# BMD101circuits.net
KiCad netlist of a schematic drawn in Altium Designer
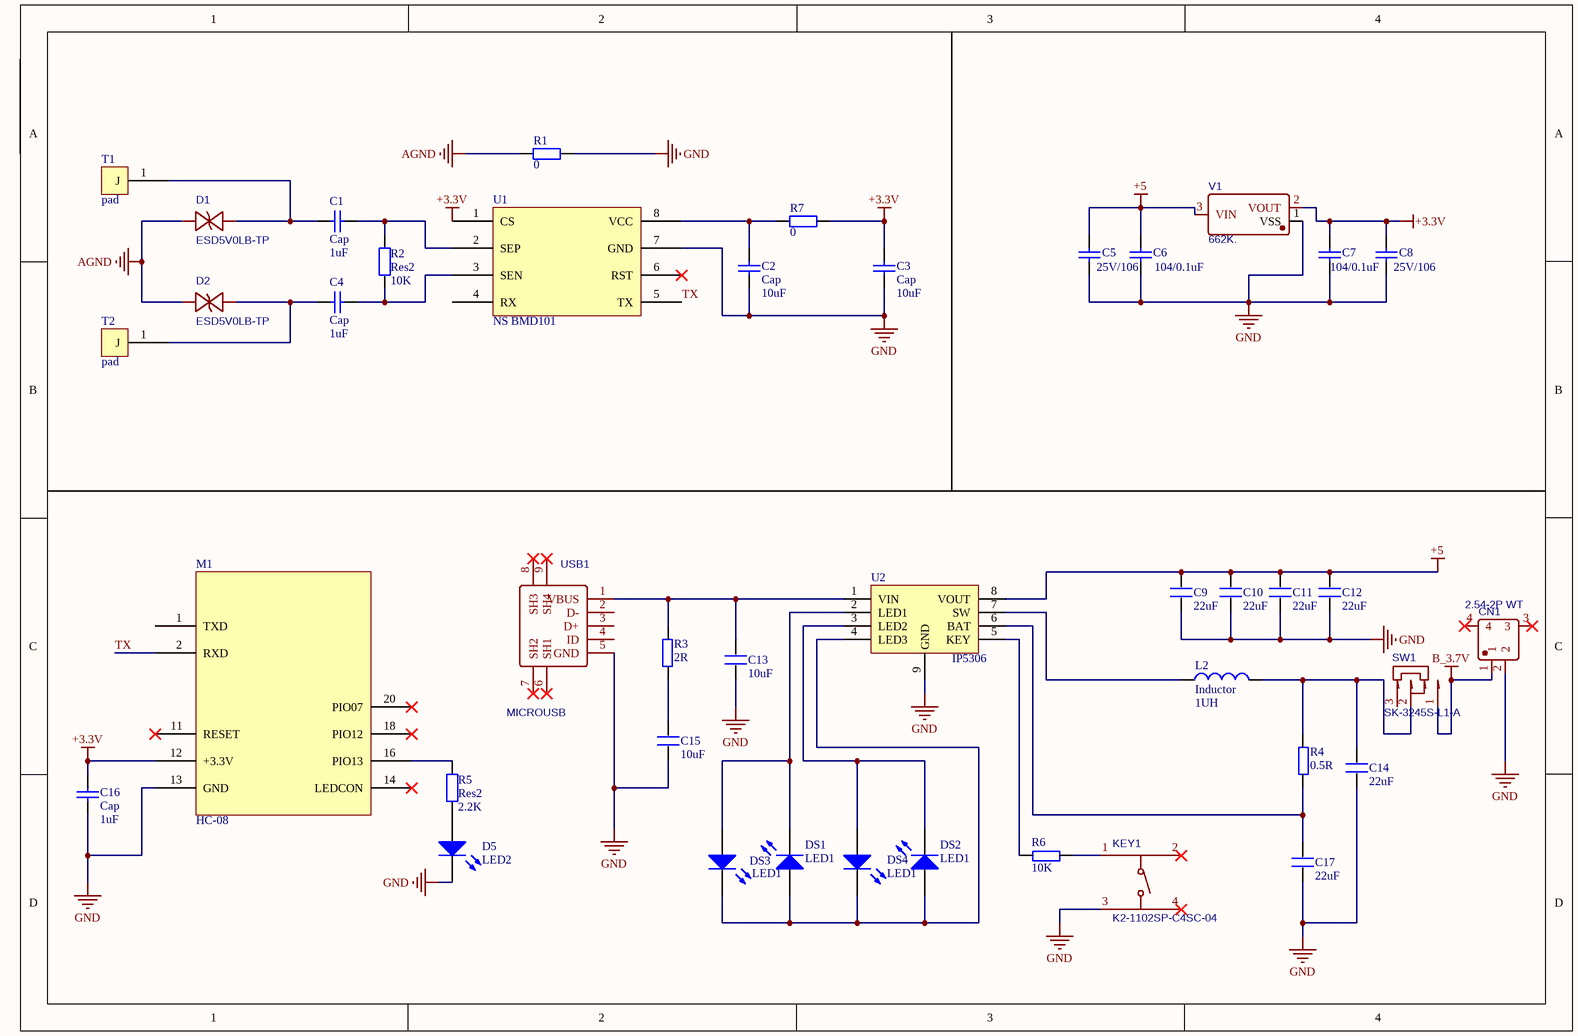
[diagram p0: BMD101circuits.SchDoc]

(export (version "E")
  (design (tool "Eeschema 10.0.6"))
  (components
    (comp (ref "C1")
      (value "Cap")
      (footprint "J1-0603")
      (description "Capacitor")
      (fields (field (name "ALTIUM_VALUE") "1uF") (field (name "PUBLISHER") "Altium Limited"))
      (libsource (lib "Miscellaneous Devices") (part "Cap"))
    )
    (comp (ref "C2")
      (value "Cap")
      (footprint "J1-0603")
      (description "Capacitor")
      (fields (field (name "ALTIUM_VALUE") "10uF") (field (name "PUBLISHER") "Altium Limited"))
      (libsource (lib "Miscellaneous Devices") (part "Cap"))
    )
    (comp (ref "C3")
      (value "Cap")
      (footprint "J1-0603")
      (description "Capacitor")
      (fields (field (name "ALTIUM_VALUE") "10uF") (field (name "PUBLISHER") "Altium Limited"))
      (libsource (lib "Miscellaneous Devices") (part "Cap"))
    )
    (comp (ref "C4")
      (value "Cap")
      (footprint "J1-0603")
      (description "Capacitor")
      (fields (field (name "ALTIUM_VALUE") "1uF") (field (name "PUBLISHER") "Altium Limited"))
      (libsource (lib "Miscellaneous Devices") (part "Cap"))
    )
    (comp (ref "C5")
      (value "25V/106")
      (footprint "J1-0603")
      (description "Capacitor")
      (fields (field (name "PUBLISHER") "Altium Limited"))
      (libsource (lib "Miscellaneous Devices") (part "Cap"))
    )
    (comp (ref "C6")
      (value "104/0.1uF")
      (footprint "J1-0603")
      (description "Capacitor")
      (fields (field (name "Comment") "104") (field (name "PUBLISHER") "Altium Limited"))
      (libsource (lib "Miscellaneous Devices") (part "Cap"))
    )
    (comp (ref "C7")
      (value "104/0.1uF")
      (footprint "J1-0603")
      (description "Capacitor")
      (fields (field (name "Comment") "104") (field (name "PUBLISHER") "Altium Limited"))
      (libsource (lib "Miscellaneous Devices") (part "Cap"))
    )
    (comp (ref "C8")
      (value "25V/106")
      (footprint "J1-0603")
      (description "Capacitor")
      (fields (field (name "PUBLISHER") "Altium Limited"))
      (libsource (lib "Miscellaneous Devices") (part "Cap"))
    )
    (comp (ref "C9")
      (value "22uF")
      (footprint "J1-0603")
      (description "0805")
      (libsource (lib "power") (part "C_22"))
    )
    (comp (ref "C10")
      (value "22uF")
      (footprint "J1-0603")
      (description "0805")
      (libsource (lib "power") (part "C_22"))
    )
    (comp (ref "C11")
      (value "22uF")
      (footprint "J1-0603")
      (description "0805")
      (libsource (lib "power") (part "C_22"))
    )
    (comp (ref "C12")
      (value "22uF")
      (footprint "J1-0603")
      (description "0805")
      (libsource (lib "power") (part "C_22"))
    )
    (comp (ref "C13")
      (value "10uF")
      (footprint "J1-0603")
      (description "0805")
      (libsource (lib "power") (part "C_22"))
    )
    (comp (ref "C14")
      (value "22uF")
      (footprint "J1-0603")
      (description "0805")
      (libsource (lib "power") (part "C_22"))
    )
    (comp (ref "C15")
      (value "10uF")
      (footprint "Miscellaneous Devices:J1-0603")
      (description "0805")
      (libsource (lib "power") (part "C_22"))
    )
    (comp (ref "C16")
      (value "Cap")
      (footprint "J1-0603")
      (description "Capacitor")
      (fields (field (name "ALTIUM_VALUE") "1uF") (field (name "PUBLISHER") "Altium Limited"))
      (libsource (lib "Miscellaneous Devices") (part "Cap"))
    )
    (comp (ref "C17")
      (value "22uF")
      (footprint "J1-0603")
      (description "0805")
      (libsource (lib "power") (part "C_22"))
    )
    (comp (ref "CN1")
      (value "2.54-2P WT")
      (footprint "CONN-SMD_2.54-2PWT")
      (fields (field (name "BOM_SUPPLIER PART") "C668622") (field (name "CONTRIBUTOR") "LCSC"))
      (libsource (lib "毕业设计") (part "2.54-2P WT"))
    )
    (comp (ref "D1")
      (value "ESD5V0LB-TP")
      (footprint "ESD5V0D5B")
      (fields (field (name "BOM_SUPPLIER PART") "C668927") (field (name "CONTRIBUTOR") "LCSC"))
      (libsource (lib "altium-import") (part "root_0_ESD5V0LB-TP_"))
    )
    (comp (ref "D2")
      (value "ESD5V0LB-TP")
      (footprint "ESD5V0D5B")
      (fields (field (name "BOM_SUPPLIER PART") "C668927") (field (name "CONTRIBUTOR") "LCSC"))
      (libsource (lib "altium-import") (part "root_2_ESD5V0LB-TP_"))
    )
    (comp (ref "D5")
      (value "LED2")
      (footprint "LED0603-FD")
      (description "Typical RED, GREEN, YELLOW, AMBER GaAs LED")
      (fields (field (name "PUBLISHER") "Altium Limited"))
      (libsource (lib "Miscellaneous Devices") (part "LED2"))
    )
    (comp (ref "DS1")
      (value "LED1")
      (footprint "LED0603-FD")
      (description "Typical RED, GREEN, YELLOW, AMBER GaAs LED")
      (fields (field (name "PUBLISHER") "Altium Limited"))
      (libsource (lib "power") (part "LED2"))
    )
    (comp (ref "DS2")
      (value "LED1")
      (footprint "LED0603-FD")
      (description "Typical RED, GREEN, YELLOW, AMBER GaAs LED")
      (fields (field (name "PUBLISHER") "Altium Limited"))
      (libsource (lib "power") (part "LED2"))
    )
    (comp (ref "DS3")
      (value "LED1")
      (footprint "LED0603-FD")
      (description "Typical RED, GREEN, YELLOW, AMBER GaAs LED")
      (fields (field (name "PUBLISHER") "Altium Limited"))
      (libsource (lib "power") (part "LED2"))
    )
    (comp (ref "DS4")
      (value "LED1")
      (footprint "LED0603-FD")
      (description "Typical RED, GREEN, YELLOW, AMBER GaAs LED")
      (fields (field (name "PUBLISHER") "Altium Limited"))
      (libsource (lib "power") (part "LED2"))
    )
    (comp (ref "KEY1")
      (value "K2-1102SP-C4SC-04")
      (footprint "KEY-SMD_4P-L6.0-W6.0-P4.50-LS9.5-BL")
      (fields (field (name "BOM_SUPPLIER PART") "C127509") (field (name "CONTRIBUTOR") "LCSC"))
      (libsource (lib "毕业设计") (part "K2-1102SP-C4SC-04"))
    )
    (comp (ref "L2")
      (value "Inductor")
      (footprint "J1-0603")
      (fields (field (name "ALTIUM_VALUE") "1UH") (field (name "PUBLISHER") "Altium Limited"))
      (libsource (lib "power") (part "Inductor"))
    )
    (comp (ref "M1")
      (value "HC-08")
      (footprint "HC-08")
      (description "BLE蓝牙通信模块")
      (libsource (lib "毕业设计") (part "HC-08"))
    )
    (comp (ref "R1")
      (value "0")
      (footprint "J1-0603")
      (description "Resistor")
      (fields (field (name "Comment") "10K") (field (name "PUBLISHER") "Altium Limited"))
      (libsource (lib "原理图库") (part "Res2"))
    )
    (comp (ref "R2")
      (value "Res2")
      (footprint "J1-0603")
      (description "Resistor")
      (fields (field (name "ALTIUM_VALUE") "10K") (field (name "PUBLISHER") "Altium Limited"))
      (libsource (lib "Miscellaneous Devices") (part "Res2"))
    )
    (comp (ref "R3")
      (value "2R")
      (footprint "Miscellaneous Devices:J1-0603")
      (libsource (lib "power") (part "R_2"))
    )
    (comp (ref "R4") (value "0.5R") (footprint "J1-0603") (libsource (lib "power") (part "R_2")))
    (comp (ref "R5")
      (value "Res2")
      (footprint "J1-0603")
      (description "Resistor")
      (fields (field (name "ALTIUM_VALUE") "2.2K") (field (name "PUBLISHER") "Altium Limited"))
      (libsource (lib "Miscellaneous Devices") (part "Res2"))
    )
    (comp (ref "R6") (value "10K") (footprint "J1-0603") (libsource (lib "power") (part "R_2")))
    (comp (ref "R7")
      (value "0")
      (footprint "J1-0603")
      (description "Resistor")
      (fields (field (name "Comment") "10K") (field (name "PUBLISHER") "Altium Limited"))
      (libsource (lib "原理图库") (part "Res2"))
    )
    (comp (ref "SW1")
      (value "SK-3245S-L1-A")
      (footprint "SW-SMD_SK-3245S-L1-A-1")
      (description "卧式滑动开关")
      (fields (field (name "BOM_SUPPLIER PART") "C405951") (field (name "CONTRIBUTOR") "LCSC"))
      (libsource (lib "毕业设计") (part "SK-3245S-L1-A"))
    )
    (comp (ref "T1") (value "pad") (footprint "BATOO") (libsource (lib "毕业设计") (part "BATOO")))
    (comp (ref "T2") (value "pad") (footprint "BATOO") (libsource (lib "毕业设计") (part "BATOO")))
    (comp (ref "U1")
      (value "NS BMD101")
      (footprint "BMD101")
      (description "NeuroSky心率芯片")
      (libsource (lib "毕业设计") (part "BMD101"))
    )
    (comp (ref "U2")
      (value "IP5306")
      (footprint "ip5306")
      (description "SOP8")
      (libsource (lib "power") (part "IP5306"))
    )
    (comp (ref "USB1")
      (value "MICROUSB")
      (footprint "MICRO-USB-SMD_MICROXNJ")
      (fields
        (field (name "BOM_SUPPLIER PART") "C404969")
        (field (name "BOM_MANUFACTURER PART") "MicroXNJ")
        (field (name "CONTRIBUTOR") "LCSC")
      )
      (libsource (lib "毕业设计") (part "MICROusb"))
    )
    (comp (ref "V1")
      (value "662K.")
      (footprint "662K")
      (fields (field (name "BOM_SUPPLIER PART") "C841298") (field (name "CONTRIBUTOR") "LCSC"))
      (libsource (lib "毕业设计") (part "662K."))
    )
  )
  (nets
    (net (code "1") (name "+3.3V") (class "Default")
      (node (ref "C16") (pin "2") (pinfunction "2_2") (pintype "passive"))
      (node (ref "C3") (pin "2") (pinfunction "2_2") (pintype "passive"))
      (node (ref "C7") (pin "1") (pinfunction "1_1") (pintype "passive"))
      (node (ref "C8") (pin "2") (pinfunction "2_2") (pintype "passive"))
      (node (ref "M1") (pin "12") (pinfunction "+3.3V_12") (pintype "passive"))
      (node (ref "R7") (pin "2") (pinfunction "2_2") (pintype "passive"))
      (node (ref "U1") (pin "1") (pinfunction "CS_1") (pintype "passive"))
      (node (ref "V1") (pin "2") (pinfunction "VOUT_2") (pintype "passive"))
    )
    (net (code "2") (name "+5") (class "Default")
      (node (ref "C10") (pin "2") (pintype "passive"))
      (node (ref "C11") (pin "2") (pintype "passive"))
      (node (ref "C12") (pin "2") (pintype "passive"))
      (node (ref "C5") (pin "2") (pinfunction "2_2") (pintype "passive"))
      (node (ref "C6") (pin "1") (pinfunction "1_1") (pintype "passive"))
      (node (ref "C9") (pin "2") (pintype "passive"))
      (node (ref "U2") (pin "8") (pinfunction "VOUT_8") (pintype "passive"))
      (node (ref "V1") (pin "3") (pinfunction "VIN_3") (pintype "passive"))
    )
    (net (code "3") (name "/TX") (class "Default")
      (node (ref "M1") (pin "2") (pinfunction "RXD_2") (pintype "passive"))
      (node (ref "U1") (pin "5") (pinfunction "TX_5") (pintype "passive"))
    )
    (net (code "4") (name "AGND") (class "Default")
      (node (ref "D1") (pin "1") (pinfunction "1_1") (pintype "passive"))
      (node (ref "D2") (pin "2") (pinfunction "2_2") (pintype "passive"))
      (node (ref "R1") (pin "1") (pinfunction "1_1") (pintype "passive"))
    )
    (net (code "5") (name "B_3.7V") (class "Default")
      (node (ref "CN1") (pin "1") (pinfunction "1_1") (pintype "passive"))
      (node (ref "SW1") (pin "1") (pinfunction "1_1") (pintype "passive"))
    )
    (net (code "6") (name "GND") (class "Default")
      (node (ref "C10") (pin "1") (pintype "passive"))
      (node (ref "C11") (pin "1") (pintype "passive"))
      (node (ref "C12") (pin "1") (pintype "passive"))
      (node (ref "C13") (pin "1") (pintype "passive"))
      (node (ref "C14") (pin "1") (pintype "passive"))
      (node (ref "C15") (pin "1") (pintype "passive"))
      (node (ref "C16") (pin "1") (pinfunction "1_1") (pintype "passive"))
      (node (ref "C17") (pin "1") (pintype "passive"))
      (node (ref "C2") (pin "1") (pinfunction "1_1") (pintype "passive"))
      (node (ref "C3") (pin "1") (pinfunction "1_1") (pintype "passive"))
      (node (ref "C5") (pin "1") (pinfunction "1_1") (pintype "passive"))
      (node (ref "C6") (pin "2") (pinfunction "2_2") (pintype "passive"))
      (node (ref "C7") (pin "2") (pinfunction "2_2") (pintype "passive"))
      (node (ref "C8") (pin "1") (pinfunction "1_1") (pintype "passive"))
      (node (ref "C9") (pin "1") (pintype "passive"))
      (node (ref "CN1") (pin "2") (pinfunction "2_2") (pintype "passive"))
      (node (ref "D5") (pin "2") (pinfunction "K_2") (pintype "passive"))
      (node (ref "KEY1") (pin "3") (pinfunction "3_3") (pintype "passive"))
      (node (ref "M1") (pin "13") (pinfunction "GND_13") (pintype "passive"))
      (node (ref "R1") (pin "2") (pinfunction "2_2") (pintype "passive"))
      (node (ref "U1") (pin "7") (pinfunction "GND_7") (pintype "passive"))
      (node (ref "U2") (pin "9") (pinfunction "GND_9") (pintype "passive"))
      (node (ref "USB1") (pin "5") (pinfunction "GND_5") (pintype "passive"))
      (node (ref "V1") (pin "1") (pinfunction "VSS_1") (pintype "passive"))
    )
    (net (code "7") (name "Net-(C14-Pad2)") (class "Default")
      (node (ref "C14") (pin "2") (pintype "passive"))
      (node (ref "L2") (pin "2") (pinfunction "2_2") (pintype "passive"))
      (node (ref "R4") (pin "2") (pintype "passive"))
      (node (ref "SW1") (pin "2") (pinfunction "2_2") (pintype "passive"))
    )
    (net (code "8") (name "Net-(C15-Pad2)") (class "Default")
      (node (ref "C15") (pin "2") (pintype "passive"))
      (node (ref "R3") (pin "2") (pintype "passive"))
    )
    (net (code "9") (name "Net-(D5-A)") (class "Default")
      (node (ref "D5") (pin "1") (pinfunction "A_1") (pintype "passive"))
      (node (ref "R5") (pin "1") (pinfunction "1_1") (pintype "passive"))
    )
    (net (code "10") (name "Net-(DS1-A)") (class "Default")
      (node (ref "DS1") (pin "1") (pinfunction "A_1") (pintype "passive"))
      (node (ref "DS2") (pin "1") (pinfunction "A_1") (pintype "passive"))
      (node (ref "DS3") (pin "2") (pinfunction "K_2") (pintype "passive"))
      (node (ref "DS4") (pin "2") (pinfunction "K_2") (pintype "passive"))
      (node (ref "U2") (pin "4") (pinfunction "LED3_4") (pintype "passive"))
    )
    (net (code "11") (name "Net-(DS1-K)") (class "Default")
      (node (ref "DS1") (pin "2") (pinfunction "K_2") (pintype "passive"))
      (node (ref "DS3") (pin "1") (pinfunction "A_1") (pintype "passive"))
      (node (ref "U2") (pin "2") (pinfunction "LED1_2") (pintype "passive"))
    )
    (net (code "12") (name "Net-(DS2-K)") (class "Default")
      (node (ref "DS2") (pin "2") (pinfunction "K_2") (pintype "passive"))
      (node (ref "DS4") (pin "1") (pinfunction "A_1") (pintype "passive"))
      (node (ref "U2") (pin "3") (pinfunction "LED2_3") (pintype "passive"))
    )
    (net (code "13") (name "Net-(KEY1-Pad1)") (class "Default")
      (node (ref "KEY1") (pin "1") (pinfunction "1_1") (pintype "passive"))
      (node (ref "R6") (pin "2") (pintype "passive"))
    )
    (net (code "14") (name "Net-(M1-PIO13)") (class "Default")
      (node (ref "M1") (pin "16") (pinfunction "PIO13_16") (pintype "passive"))
      (node (ref "R5") (pin "2") (pinfunction "2_2") (pintype "passive"))
    )
    (net (code "15") (name "Net-(T1-J)") (class "Default")
      (node (ref "C1") (pin "1") (pinfunction "1_1") (pintype "passive"))
      (node (ref "D1") (pin "2") (pinfunction "2_2") (pintype "passive"))
      (node (ref "T1") (pin "1") (pinfunction "J_1") (pintype "passive"))
    )
    (net (code "16") (name "Net-(T2-J)") (class "Default")
      (node (ref "C4") (pin "1") (pinfunction "1_1") (pintype "passive"))
      (node (ref "D2") (pin "1") (pinfunction "1_1") (pintype "passive"))
      (node (ref "T2") (pin "1") (pinfunction "J_1") (pintype "passive"))
    )
    (net (code "17") (name "Net-(U1-SEN)") (class "Default")
      (node (ref "C4") (pin "2") (pinfunction "2_2") (pintype "passive"))
      (node (ref "R2") (pin "1") (pinfunction "1_1") (pintype "passive"))
      (node (ref "U1") (pin "3") (pinfunction "SEN_3") (pintype "passive"))
    )
    (net (code "18") (name "Net-(U1-SEP)") (class "Default")
      (node (ref "C1") (pin "2") (pinfunction "2_2") (pintype "passive"))
      (node (ref "R2") (pin "2") (pinfunction "2_2") (pintype "passive"))
      (node (ref "U1") (pin "2") (pinfunction "SEP_2") (pintype "passive"))
    )
    (net (code "19") (name "Net-(U1-VCC)") (class "Default")
      (node (ref "C2") (pin "2") (pinfunction "2_2") (pintype "passive"))
      (node (ref "R7") (pin "1") (pinfunction "1_1") (pintype "passive"))
      (node (ref "U1") (pin "8") (pinfunction "VCC_8") (pintype "passive"))
    )
    (net (code "20") (name "Net-(U2-BAT)") (class "Default")
      (node (ref "C17") (pin "2") (pintype "passive"))
      (node (ref "R4") (pin "1") (pintype "passive"))
      (node (ref "U2") (pin "6") (pinfunction "BAT_6") (pintype "passive"))
    )
    (net (code "21") (name "Net-(U2-KEY)") (class "Default")
      (node (ref "R6") (pin "1") (pintype "passive"))
      (node (ref "U2") (pin "5") (pinfunction "KEY_5") (pintype "passive"))
    )
    (net (code "22") (name "Net-(U2-SW)") (class "Default")
      (node (ref "L2") (pin "1") (pinfunction "1_1") (pintype "passive"))
      (node (ref "U2") (pin "7") (pinfunction "SW_7") (pintype "passive"))
    )
    (net (code "23") (name "Net-(U2-VIN)") (class "Default")
      (node (ref "C13") (pin "2") (pintype "passive"))
      (node (ref "R3") (pin "1") (pintype "passive"))
      (node (ref "U2") (pin "1") (pinfunction "VIN_1") (pintype "passive"))
      (node (ref "USB1") (pin "1") (pinfunction "VBUS_1") (pintype "passive"))
    )
    (net (code "24") (name "unconnected-(CN1-Pad3)") (class "Default")
      (node (ref "CN1") (pin "3") (pinfunction "3_3") (pintype "passive+no_connect"))
    )
    (net (code "25") (name "unconnected-(CN1-Pad4)") (class "Default")
      (node (ref "CN1") (pin "4") (pinfunction "4_4") (pintype "passive+no_connect"))
    )
    (net (code "26") (name "unconnected-(KEY1-Pad2)") (class "Default")
      (node (ref "KEY1") (pin "2") (pinfunction "2_2") (pintype "passive+no_connect"))
    )
    (net (code "27") (name "unconnected-(KEY1-Pad4)") (class "Default")
      (node (ref "KEY1") (pin "4") (pinfunction "4_4") (pintype "passive+no_connect"))
    )
    (net (code "28") (name "unconnected-(M1-LEDCON-Pad14)") (class "Default")
      (node (ref "M1") (pin "14") (pinfunction "LEDCON_14") (pintype "passive+no_connect"))
    )
    (net (code "29") (name "unconnected-(M1-PIO07-Pad20)") (class "Default")
      (node (ref "M1") (pin "20") (pinfunction "PIO07_20") (pintype "passive+no_connect"))
    )
    (net (code "30") (name "unconnected-(M1-PIO12-Pad18)") (class "Default")
      (node (ref "M1") (pin "18") (pinfunction "PIO12_18") (pintype "passive+no_connect"))
    )
    (net (code "31") (name "unconnected-(M1-RESET-Pad11)") (class "Default")
      (node (ref "M1") (pin "11") (pinfunction "RESET_11") (pintype "passive+no_connect"))
    )
    (net (code "32") (name "unconnected-(M1-TXD-Pad1)") (class "Default")
      (node (ref "M1") (pin "1") (pinfunction "TXD_1") (pintype "passive"))
    )
    (net (code "33") (name "unconnected-(SW1-Pad3)") (class "Default")
      (node (ref "SW1") (pin "3") (pinfunction "3_3") (pintype "passive"))
    )
    (net (code "34") (name "unconnected-(U1-RST-Pad6)") (class "Default")
      (node (ref "U1") (pin "6") (pinfunction "RST_6") (pintype "passive+no_connect"))
    )
    (net (code "35") (name "unconnected-(U1-RX-Pad4)") (class "Default")
      (node (ref "U1") (pin "4") (pinfunction "RX_4") (pintype "passive"))
    )
    (net (code "36") (name "unconnected-(USB1-D+-Pad3)") (class "Default")
      (node (ref "USB1") (pin "3") (pinfunction "D+_3") (pintype "passive"))
    )
    (net (code "37") (name "unconnected-(USB1-D--Pad2)") (class "Default")
      (node (ref "USB1") (pin "2") (pinfunction "D-_2") (pintype "passive"))
    )
    (net (code "38") (name "unconnected-(USB1-ID-Pad4)") (class "Default")
      (node (ref "USB1") (pin "4") (pinfunction "ID_4") (pintype "passive"))
    )
    (net (code "39") (name "unconnected-(USB1-SH1-Pad6)") (class "Default")
      (node (ref "USB1") (pin "6") (pinfunction "SH1_6") (pintype "passive+no_connect"))
    )
    (net (code "40") (name "unconnected-(USB1-SH2-Pad7)") (class "Default")
      (node (ref "USB1") (pin "7") (pinfunction "SH2_7") (pintype "passive+no_connect"))
    )
    (net (code "41") (name "unconnected-(USB1-SH3-Pad8)") (class "Default")
      (node (ref "USB1") (pin "8") (pinfunction "SH3_8") (pintype "passive+no_connect"))
    )
    (net (code "42") (name "unconnected-(USB1-SH4-Pad9)") (class "Default")
      (node (ref "USB1") (pin "9") (pinfunction "SH4_9") (pintype "passive+no_connect"))
    )
  )
)
